# RS485.net
KiCad netlist of a schematic drawn in Altium Designer
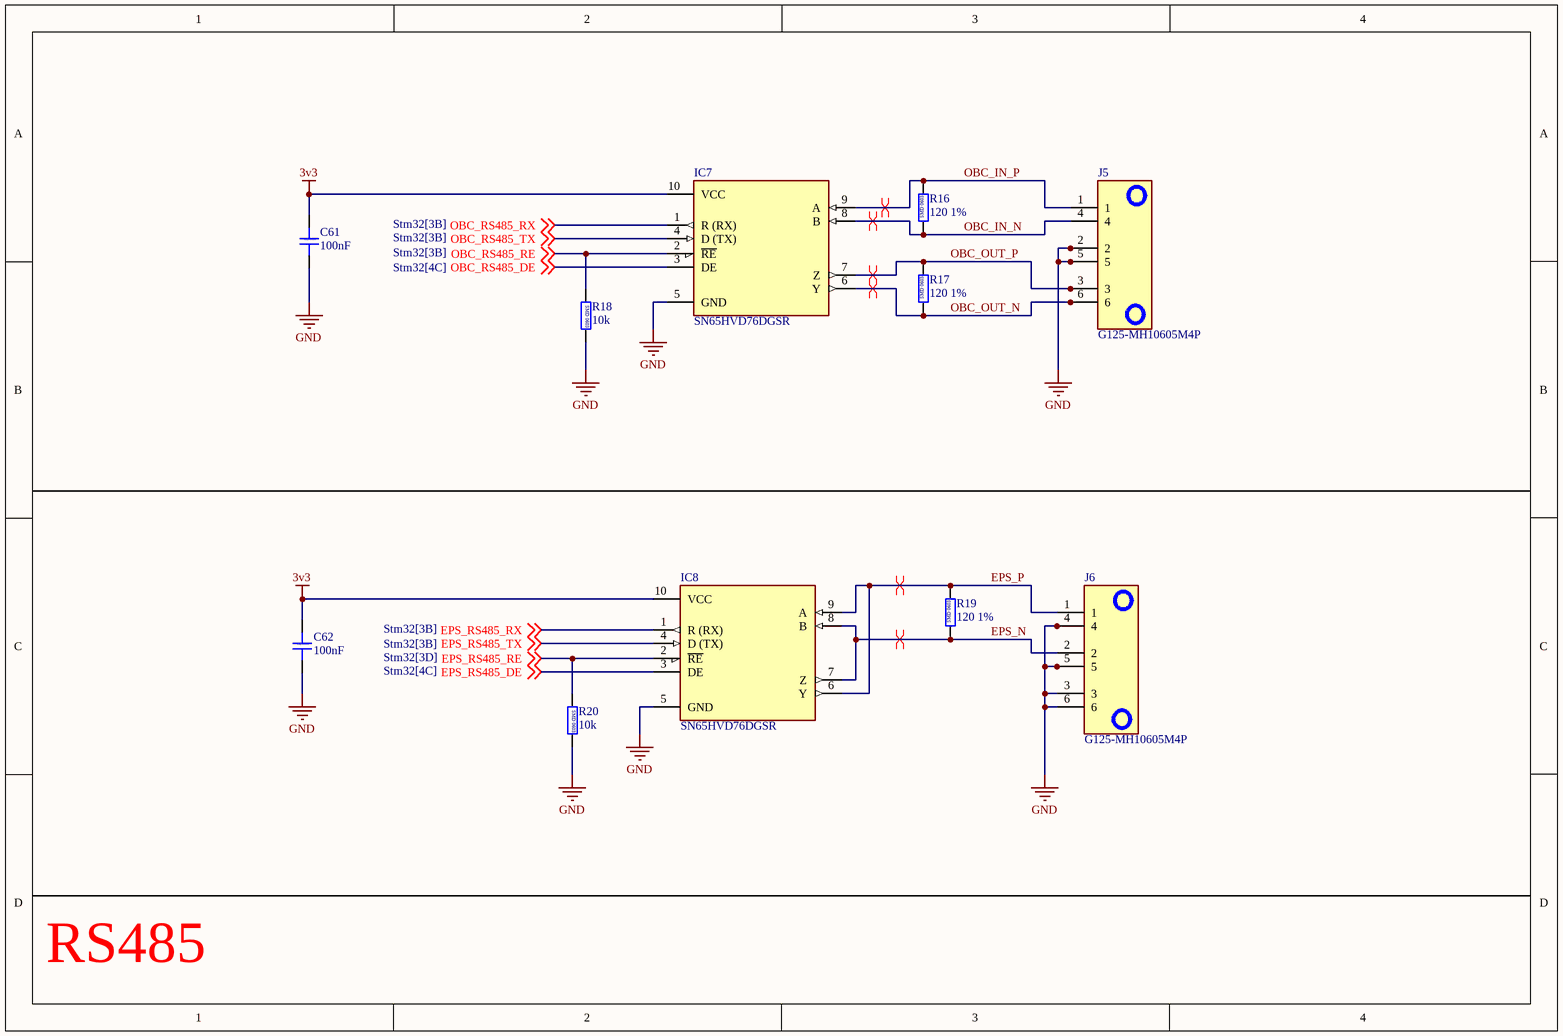
[diagram p0: RS485.SchDoc]

(export (version "E")
  (design (tool "Eeschema 10.0.6"))
  (components
    (comp (ref "C61")
      (value "100nF")
      (footprint "CAP_0603")
      (description "Capacitor SMD 0603 RATED")
      (libsource (lib "STeRG-Passives-Standard") (part "Capacitor-SMD-0603"))
    )
    (comp (ref "C62")
      (value "100nF")
      (footprint "CAP_0603")
      (description "Capacitor SMD 0603 RATED")
      (libsource (lib "STeRG-Passives-Standard") (part "Capacitor-SMD-0603"))
    )
    (comp (ref "IC7")
      (value "SN65HVD76DGSR")
      (footprint "SOP50P490X110-10N")
      (description "RS485 Full Duplex Transciever")
      (fields (field (name "MOUSER PART NUMBER") "595-SN65HVD76DGSR"))
      (libsource (lib "STeRG-ICs-Standard") (part "SN65HVD76DGSR"))
    )
    (comp (ref "IC8")
      (value "SN65HVD76DGSR")
      (footprint "SOP50P490X110-10N")
      (description "RS485 Full Duplex Transciever")
      (fields (field (name "MOUSER PART NUMBER") "595-SN65HVD76DGSR"))
      (libsource (lib "STeRG-ICs-Standard") (part "SN65HVD76DGSR"))
    )
    (comp (ref "J5")
      (value "G125-MH10605M4P")
      (footprint "G125-MH10605M4P_1")
      (description "Connector")
      (fields (field (name "MOUSER PART NUMBER") "855-G125MH1065M4PM4P"))
      (libsource (lib "STeRG-Passives-Standard") (part "G125-MH10605M4P"))
    )
    (comp (ref "J6")
      (value "G125-MH10605M4P")
      (footprint "G125-MH10605M4P_1")
      (description "Connector")
      (fields (field (name "MOUSER PART NUMBER") "855-G125MH1065M4PM4P"))
      (libsource (lib "STeRG-Passives-Standard") (part "G125-MH10605M4P"))
    )
    (comp (ref "R16")
      (value "120 1%")
      (footprint "RES_0603")
      (description "Resistor SMD 0603 RATED")
      (libsource (lib "STeRG-Passives-Standard") (part "Resistor-SMD-0603"))
    )
    (comp (ref "R17")
      (value "120 1%")
      (footprint "RES_0603")
      (description "Resistor SMD 0603 RATED")
      (libsource (lib "STeRG-Passives-Standard") (part "Resistor-SMD-0603"))
    )
    (comp (ref "R18")
      (value "10k")
      (footprint "RES_0603")
      (description "Resistor SMD 0603 RATED")
      (libsource (lib "STeRG-Passives-Standard") (part "Resistor-SMD-0603"))
    )
    (comp (ref "R19")
      (value "120 1%")
      (footprint "RES_0603")
      (description "Resistor SMD 0603 RATED")
      (libsource (lib "STeRG-Passives-Standard") (part "Resistor-SMD-0603"))
    )
    (comp (ref "R20")
      (value "10k")
      (footprint "RES_0603")
      (description "Resistor SMD 0603 RATED")
      (libsource (lib "STeRG-Passives-Standard") (part "Resistor-SMD-0603"))
    )
  )
  (nets
    (net (code "1") (name "/EPS_N") (class "Default")
      (node (ref "IC8") (pin "7") (pinfunction "Z_7") (pintype "output"))
      (node (ref "IC8") (pin "8") (pinfunction "B_8") (pintype "input"))
      (node (ref "J6") (pin "2") (pinfunction "2_2") (pintype "passive"))
      (node (ref "R19") (pin "1") (pinfunction "1_1") (pintype "passive"))
    )
    (net (code "2") (name "/EPS_P") (class "Default")
      (node (ref "IC8") (pin "6") (pinfunction "Y_6") (pintype "output"))
      (node (ref "IC8") (pin "9") (pinfunction "A_9") (pintype "input"))
      (node (ref "J6") (pin "1") (pinfunction "1_1") (pintype "passive"))
      (node (ref "R19") (pin "2") (pinfunction "2_2") (pintype "passive"))
    )
    (net (code "3") (name "/OBC_IN_N") (class "Default")
      (node (ref "IC7") (pin "8") (pinfunction "B_8") (pintype "input"))
      (node (ref "J5") (pin "4") (pinfunction "4_4") (pintype "passive"))
      (node (ref "R16") (pin "1") (pinfunction "1_1") (pintype "passive"))
    )
    (net (code "4") (name "/OBC_IN_P") (class "Default")
      (node (ref "IC7") (pin "9") (pinfunction "A_9") (pintype "input"))
      (node (ref "J5") (pin "1") (pinfunction "1_1") (pintype "passive"))
      (node (ref "R16") (pin "2") (pinfunction "2_2") (pintype "passive"))
    )
    (net (code "5") (name "/OBC_OUT_N") (class "Default")
      (node (ref "IC7") (pin "6") (pinfunction "Y_6") (pintype "output"))
      (node (ref "J5") (pin "6") (pinfunction "6_6") (pintype "passive"))
      (node (ref "R17") (pin "1") (pinfunction "1_1") (pintype "passive"))
    )
    (net (code "6") (name "/OBC_OUT_P") (class "Default")
      (node (ref "IC7") (pin "7") (pinfunction "Z_7") (pintype "output"))
      (node (ref "J5") (pin "3") (pinfunction "3_3") (pintype "passive"))
      (node (ref "R17") (pin "2") (pinfunction "2_2") (pintype "passive"))
    )
    (net (code "7") (name "3v3") (class "Default")
      (node (ref "C61") (pin "1") (pinfunction "1_1") (pintype "passive"))
      (node (ref "C62") (pin "1") (pinfunction "1_1") (pintype "passive"))
      (node (ref "IC7") (pin "10") (pinfunction "VCC_10") (pintype "passive"))
      (node (ref "IC8") (pin "10") (pinfunction "VCC_10") (pintype "passive"))
    )
    (net (code "8") (name "EPS_RS485_DE") (class "Default")
      (node (ref "IC8") (pin "3") (pinfunction "DE_3") (pintype "passive"))
    )
    (net (code "9") (name "EPS_RS485_RE") (class "Default")
      (node (ref "IC8") (pin "2") (pinfunction "~{RE}_2") (pintype "passive"))
      (node (ref "R20") (pin "1") (pinfunction "1_1") (pintype "passive"))
    )
    (net (code "10") (name "EPS_RS485_RX") (class "Default")
      (node (ref "IC8") (pin "1") (pinfunction "R_(RX)_1") (pintype "output"))
    )
    (net (code "11") (name "EPS_RS485_TX") (class "Default")
      (node (ref "IC8") (pin "4") (pinfunction "D_(TX)_4") (pintype "input"))
    )
    (net (code "12") (name "GND") (class "Default")
      (node (ref "C61") (pin "2") (pinfunction "2_2") (pintype "passive"))
      (node (ref "C62") (pin "2") (pinfunction "2_2") (pintype "passive"))
      (node (ref "IC7") (pin "5") (pinfunction "GND_5") (pintype "passive"))
      (node (ref "IC8") (pin "5") (pinfunction "GND_5") (pintype "passive"))
      (node (ref "J5") (pin "2") (pinfunction "2_2") (pintype "passive"))
      (node (ref "J5") (pin "5") (pinfunction "5_5") (pintype "passive"))
      (node (ref "J6") (pin "3") (pinfunction "3_3") (pintype "passive"))
      (node (ref "J6") (pin "4") (pinfunction "4_4") (pintype "passive"))
      (node (ref "J6") (pin "5") (pinfunction "5_5") (pintype "passive"))
      (node (ref "J6") (pin "6") (pinfunction "6_6") (pintype "passive"))
      (node (ref "R18") (pin "2") (pinfunction "2_2") (pintype "passive"))
      (node (ref "R20") (pin "2") (pinfunction "2_2") (pintype "passive"))
    )
    (net (code "13") (name "OBC_RS485_DE") (class "Default")
      (node (ref "IC7") (pin "3") (pinfunction "DE_3") (pintype "passive"))
    )
    (net (code "14") (name "OBC_RS485_RE") (class "Default")
      (node (ref "IC7") (pin "2") (pinfunction "~{RE}_2") (pintype "passive"))
      (node (ref "R18") (pin "1") (pinfunction "1_1") (pintype "passive"))
    )
    (net (code "15") (name "OBC_RS485_RX") (class "Default")
      (node (ref "IC7") (pin "1") (pinfunction "R_(RX)_1") (pintype "output"))
    )
    (net (code "16") (name "OBC_RS485_TX") (class "Default")
      (node (ref "IC7") (pin "4") (pinfunction "D_(TX)_4") (pintype "input"))
    )
  )
)
